# T412_finalproj.net
KiCad netlist of a schematic drawn in EAGLE
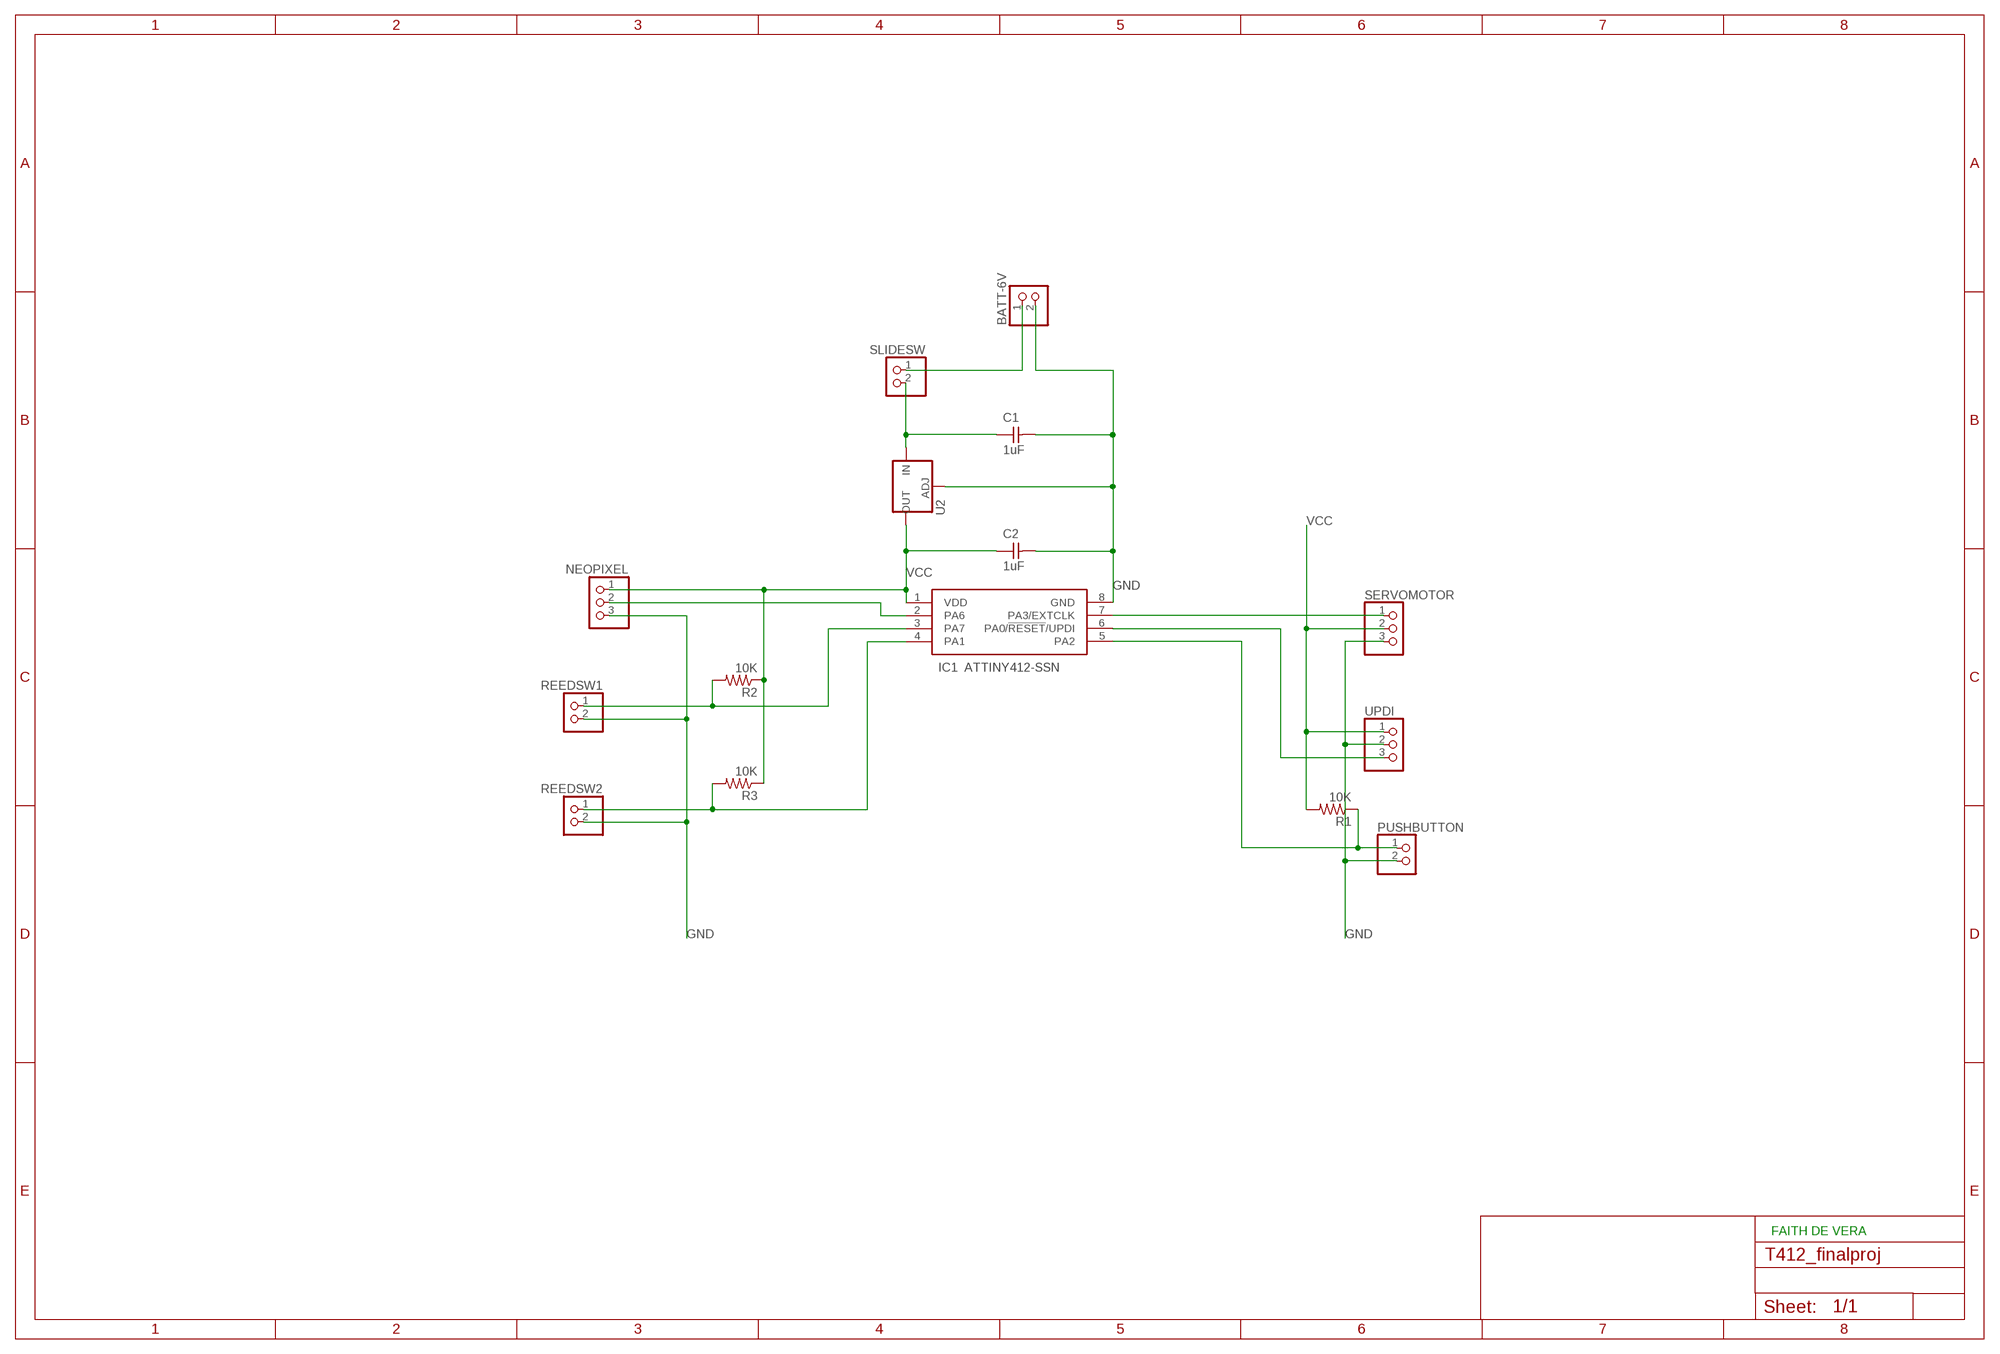
[diagram p0: schematic, sheet 1]

(export (version "E")
  (design (tool "Eeschema 10.0.6"))
  (components
    (comp (ref "BATT-6V")
      (value "PINHD-1X2")
      (footprint "eagle-import:1X02")
      (libsource (lib "eagle-import") (part "PINHD-1X2"))
    )
    (comp (ref "C1")
      (value "1uF")
      (footprint "eagle-import:C1206FAB")
      (libsource (lib "eagle-import") (part "CAP_UNPOLARIZEDFAB"))
    )
    (comp (ref "C2")
      (value "1uF")
      (footprint "eagle-import:C1206FAB")
      (libsource (lib "eagle-import") (part "CAP_UNPOLARIZEDFAB"))
    )
    (comp (ref "IC1")
      (value "ATTINY412-SSN")
      (footprint "eagle-import:SOIC127P600X175-8N")
      (fields (field (name "MOUSER_PART_NUMBER") "579-ATTINY412-SSN"))
      (libsource (lib "eagle-import") (part "ATTINY412-SSN"))
    )
    (comp (ref "NEOPIXEL")
      (value "PINHD-1X3")
      (footprint "eagle-import:1X03")
      (libsource (lib "eagle-import") (part "PINHD-1X3"))
    )
    (comp (ref "PUSHBUTTON")
      (value "PINHD-1X2")
      (footprint "eagle-import:1X02")
      (libsource (lib "eagle-import") (part "PINHD-1X2"))
    )
    (comp (ref "R1")
      (value "10K")
      (footprint "eagle-import:R1206FAB")
      (libsource (lib "eagle-import") (part "R1206FAB"))
    )
    (comp (ref "R2")
      (value "10K")
      (footprint "eagle-import:R1206FAB")
      (libsource (lib "eagle-import") (part "R1206FAB"))
    )
    (comp (ref "R3")
      (value "10K")
      (footprint "eagle-import:R1206FAB")
      (libsource (lib "eagle-import") (part "R1206FAB"))
    )
    (comp (ref "REEDSW1")
      (value "PINHD-1X2")
      (footprint "eagle-import:1X02")
      (libsource (lib "eagle-import") (part "PINHD-1X2"))
    )
    (comp (ref "REEDSW2")
      (value "PINHD-1X2")
      (footprint "eagle-import:1X02")
      (libsource (lib "eagle-import") (part "PINHD-1X2"))
    )
    (comp (ref "SERVOMOTOR")
      (value "PINHD-1X3")
      (footprint "eagle-import:1X03")
      (libsource (lib "eagle-import") (part "PINHD-1X3"))
    )
    (comp (ref "SLIDESW")
      (value "PINHD-1X2")
      (footprint "eagle-import:1X02")
      (libsource (lib "eagle-import") (part "PINHD-1X2"))
    )
    (comp (ref "U2")
      (value "V_REG_LM1117SOT223")
      (footprint "eagle-import:SOT223")
      (libsource (lib "eagle-import") (part "V_REG_LM1117SOT223"))
    )
    (comp (ref "UPDI")
      (value "PINHD-1X3")
      (footprint "eagle-import:1X03")
      (libsource (lib "eagle-import") (part "PINHD-1X3"))
    )
  )
  (nets
    (net (code "1") (name "/GND") (class "Default")
      (node (ref "BATT-6V") (pin "2") (pinfunction "2_2") (pintype "passive"))
      (node (ref "C1") (pin "2") (pinfunction "2_2") (pintype "passive"))
      (node (ref "C2") (pin "2") (pinfunction "2_2") (pintype "passive"))
      (node (ref "IC1") (pin "8") (pinfunction "GND_8") (pintype "bidirectional"))
      (node (ref "NEOPIXEL") (pin "3") (pinfunction "3_3") (pintype "passive"))
      (node (ref "PUSHBUTTON") (pin "2") (pinfunction "2_2") (pintype "passive"))
      (node (ref "REEDSW1") (pin "2") (pinfunction "2_2") (pintype "passive"))
      (node (ref "REEDSW2") (pin "2") (pinfunction "2_2") (pintype "passive"))
      (node (ref "SERVOMOTOR") (pin "3") (pinfunction "3_3") (pintype "passive"))
      (node (ref "U2") (pin "1") (pinfunction "ADJ_1") (pintype "input"))
      (node (ref "UPDI") (pin "2") (pinfunction "2_2") (pintype "passive"))
    )
    (net (code "2") (name "/VCC") (class "Default")
      (node (ref "C2") (pin "1") (pinfunction "1_1") (pintype "passive"))
      (node (ref "IC1") (pin "1") (pinfunction "VDD_1") (pintype "bidirectional"))
      (node (ref "NEOPIXEL") (pin "1") (pinfunction "1_1") (pintype "passive"))
      (node (ref "R1") (pin "2") (pinfunction "2_2") (pintype "passive"))
      (node (ref "R2") (pin "1") (pinfunction "1_1") (pintype "passive"))
      (node (ref "R3") (pin "1") (pinfunction "1_1") (pintype "passive"))
      (node (ref "SERVOMOTOR") (pin "2") (pinfunction "2_2") (pintype "passive"))
      (node (ref "U2") (pin "2") (pinfunction "OUT_2") (pintype "output"))
      (node (ref "U2") (pin "4") (pinfunction "OUT_4") (pintype "output"))
      (node (ref "UPDI") (pin "1") (pinfunction "1_1") (pintype "passive"))
    )
    (net (code "3") (name "Net-(BATT-6V-Pad1)") (class "Default")
      (node (ref "BATT-6V") (pin "1") (pinfunction "1_1") (pintype "passive"))
      (node (ref "SLIDESW") (pin "1") (pinfunction "1_1") (pintype "passive"))
    )
    (net (code "4") (name "Net-(IC1-PA0{slash}~{RESET}{slash}UPDI)") (class "Default")
      (node (ref "IC1") (pin "6") (pinfunction "PA0/~{RESET}/UPDI_6") (pintype "bidirectional"))
      (node (ref "UPDI") (pin "3") (pinfunction "3_3") (pintype "passive"))
    )
    (net (code "5") (name "Net-(IC1-PA1)") (class "Default")
      (node (ref "IC1") (pin "4") (pinfunction "PA1_4") (pintype "bidirectional"))
      (node (ref "R3") (pin "2") (pinfunction "2_2") (pintype "passive"))
      (node (ref "REEDSW2") (pin "1") (pinfunction "1_1") (pintype "passive"))
    )
    (net (code "6") (name "Net-(IC1-PA2)") (class "Default")
      (node (ref "IC1") (pin "5") (pinfunction "PA2_5") (pintype "bidirectional"))
      (node (ref "PUSHBUTTON") (pin "1") (pinfunction "1_1") (pintype "passive"))
      (node (ref "R1") (pin "1") (pinfunction "1_1") (pintype "passive"))
    )
    (net (code "7") (name "Net-(IC1-PA3{slash}EXTCLK)") (class "Default")
      (node (ref "IC1") (pin "7") (pinfunction "PA3/EXTCLK_7") (pintype "bidirectional"))
      (node (ref "SERVOMOTOR") (pin "1") (pinfunction "1_1") (pintype "passive"))
    )
    (net (code "8") (name "Net-(IC1-PA6)") (class "Default")
      (node (ref "IC1") (pin "2") (pinfunction "PA6_2") (pintype "bidirectional"))
      (node (ref "NEOPIXEL") (pin "2") (pinfunction "2_2") (pintype "passive"))
    )
    (net (code "9") (name "Net-(IC1-PA7)") (class "Default")
      (node (ref "IC1") (pin "3") (pinfunction "PA7_3") (pintype "bidirectional"))
      (node (ref "R2") (pin "2") (pinfunction "2_2") (pintype "passive"))
      (node (ref "REEDSW1") (pin "1") (pinfunction "1_1") (pintype "passive"))
    )
    (net (code "10") (name "Net-(U2-IN)") (class "Default")
      (node (ref "C1") (pin "1") (pinfunction "1_1") (pintype "passive"))
      (node (ref "SLIDESW") (pin "2") (pinfunction "2_2") (pintype "passive"))
      (node (ref "U2") (pin "3") (pinfunction "IN_3") (pintype "input"))
    )
  )
)
